# speculator_minor_breakout_54mm_v1.net
KiCad netlist of a schematic drawn in EAGLE
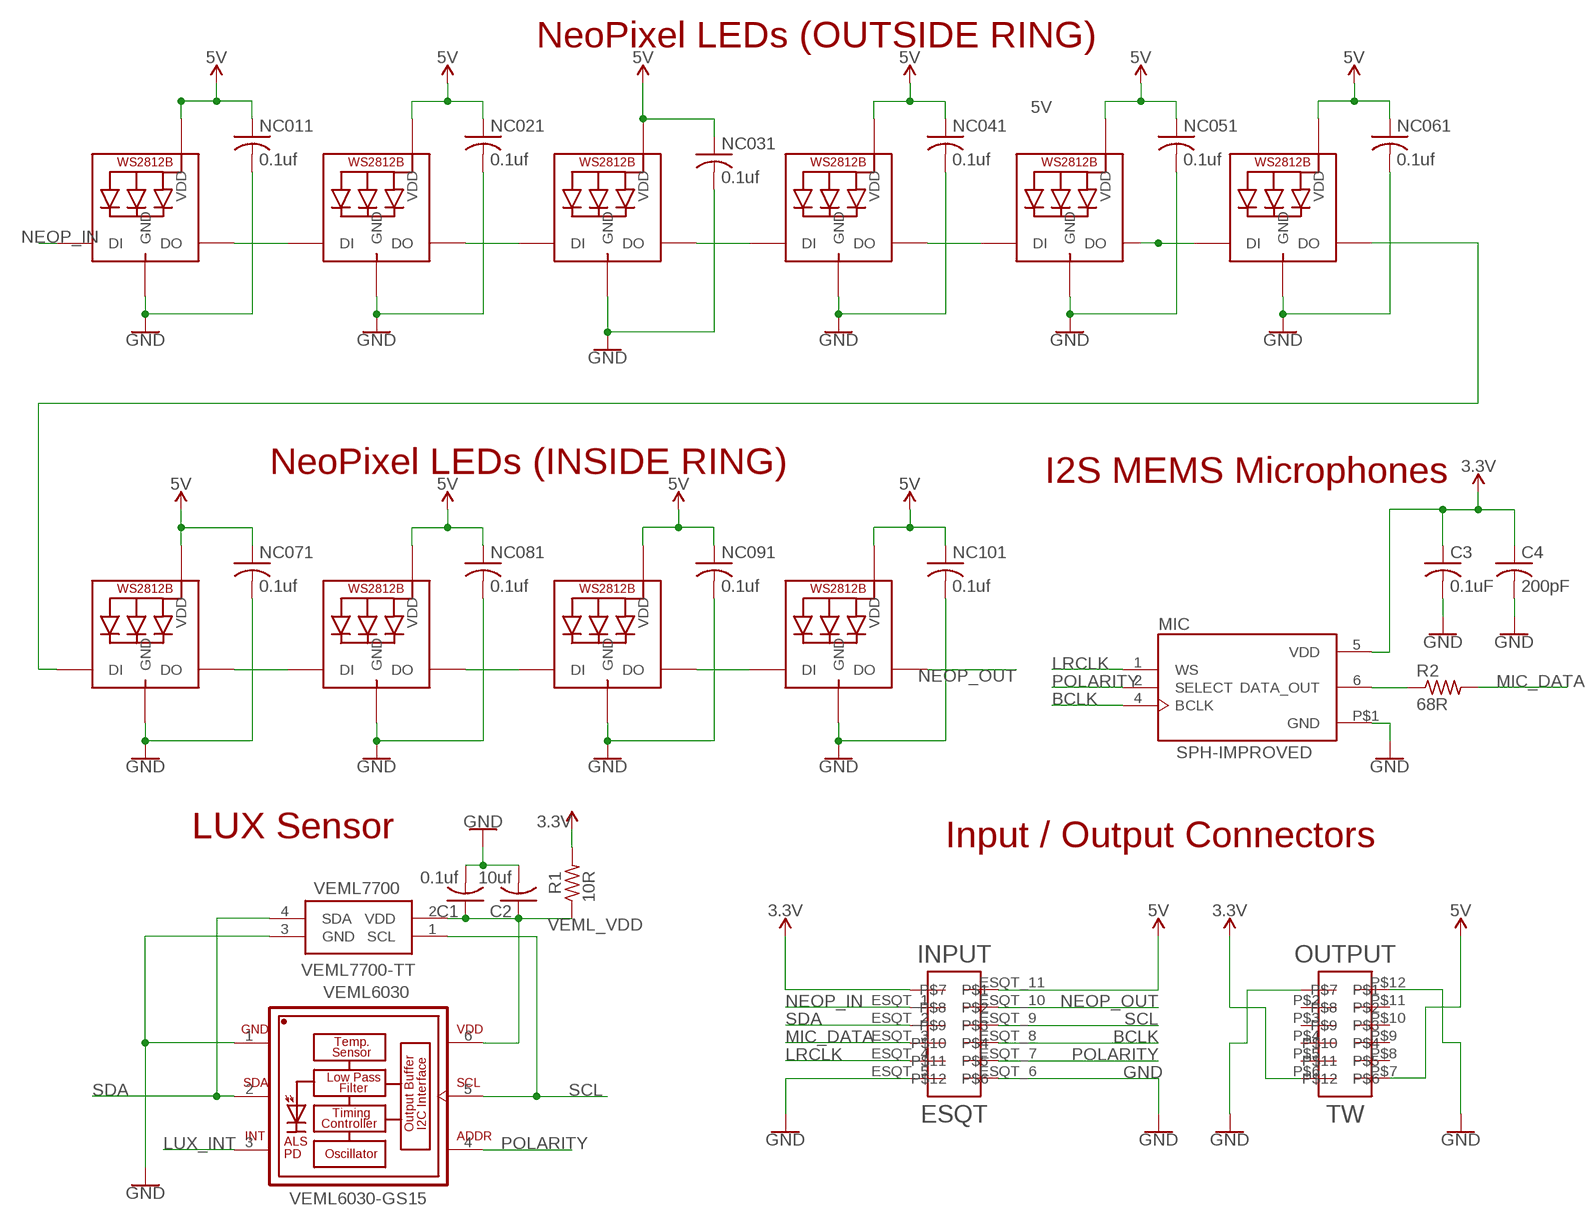
[diagram p0: schematic, sheet 1]

(export (version "E")
  (design (tool "Eeschema 10.0.6"))
  (components
    (comp (ref "C1")
      (value "0.1uf")
      (footprint "eagle-import:C0805")
      (libsource (lib "eagle-import") (part "C-USC0805"))
    )
    (comp (ref "C2")
      (value "10uf")
      (footprint "eagle-import:C0805")
      (libsource (lib "eagle-import") (part "C-USC0805"))
    )
    (comp (ref "C3")
      (value "0.1uF")
      (footprint "eagle-import:C0805")
      (libsource (lib "eagle-import") (part "C-USC0805"))
    )
    (comp (ref "C4")
      (value "200pF")
      (footprint "eagle-import:C0805")
      (libsource (lib "eagle-import") (part "C-USC0805"))
    )
    (comp (ref "INPUT")
      (value "ESQT")
      (footprint "eagle-import:SAMTEC_ESQT_2X6_THROUGH_HOLE")
      (libsource (lib "eagle-import") (part "SAMTEC_ESQT_2X6_THROUGH_HOLE"))
    )
    (comp (ref "MIC")
      (value "SPH-IMPROVED")
      (footprint "eagle-import:MIC_SPH0645LM4H-B_LARGER_RING")
      (libsource (lib "eagle-import") (part "SPH-IMPROVED"))
    )
    (comp (ref "NC011")
      (value "0.1uf")
      (footprint "eagle-import:C0805K")
      (libsource (lib "eagle-import") (part "C-USC0805K"))
    )
    (comp (ref "NC021")
      (value "0.1uf")
      (footprint "eagle-import:C0805K")
      (libsource (lib "eagle-import") (part "C-USC0805K"))
    )
    (comp (ref "NC031")
      (value "0.1uf")
      (footprint "eagle-import:C0805K")
      (libsource (lib "eagle-import") (part "C-USC0805K"))
    )
    (comp (ref "NC041")
      (value "0.1uf")
      (footprint "eagle-import:C0805K")
      (libsource (lib "eagle-import") (part "C-USC0805K"))
    )
    (comp (ref "NC051")
      (value "0.1uf")
      (footprint "eagle-import:C0805K")
      (libsource (lib "eagle-import") (part "C-USC0805K"))
    )
    (comp (ref "NC061")
      (value "0.1uf")
      (footprint "eagle-import:C0805K")
      (libsource (lib "eagle-import") (part "C-USC0805K"))
    )
    (comp (ref "NC071")
      (value "0.1uf")
      (footprint "eagle-import:C0805K")
      (libsource (lib "eagle-import") (part "C-USC0805K"))
    )
    (comp (ref "NC081")
      (value "0.1uf")
      (footprint "eagle-import:C0805K")
      (libsource (lib "eagle-import") (part "C-USC0805K"))
    )
    (comp (ref "NC091")
      (value "0.1uf")
      (footprint "eagle-import:C0805K")
      (libsource (lib "eagle-import") (part "C-USC0805K"))
    )
    (comp (ref "NC101")
      (value "0.1uf")
      (footprint "eagle-import:C0805K")
      (libsource (lib "eagle-import") (part "C-USC0805K"))
    )
    (comp (ref "NEO1")
      (value "WS2812B5050")
      (footprint "eagle-import:WS2812B")
      (libsource (lib "eagle-import") (part "WS2812B5050"))
    )
    (comp (ref "NEO2")
      (value "WS2812B5050")
      (footprint "eagle-import:WS2812B")
      (libsource (lib "eagle-import") (part "WS2812B5050"))
    )
    (comp (ref "NEO3")
      (value "WS2812B5050")
      (footprint "eagle-import:WS2812B")
      (libsource (lib "eagle-import") (part "WS2812B5050"))
    )
    (comp (ref "NEO4")
      (value "WS2812B5050")
      (footprint "eagle-import:WS2812B")
      (libsource (lib "eagle-import") (part "WS2812B5050"))
    )
    (comp (ref "NEO5")
      (value "WS2812B5050")
      (footprint "eagle-import:WS2812B")
      (libsource (lib "eagle-import") (part "WS2812B5050"))
    )
    (comp (ref "NEO6")
      (value "WS2812B5050")
      (footprint "eagle-import:WS2812B")
      (libsource (lib "eagle-import") (part "WS2812B5050"))
    )
    (comp (ref "NEO07")
      (value "WS2812B5050")
      (footprint "eagle-import:WS2812B")
      (libsource (lib "eagle-import") (part "WS2812B5050"))
    )
    (comp (ref "NEO08")
      (value "WS2812B5050")
      (footprint "eagle-import:WS2812B")
      (libsource (lib "eagle-import") (part "WS2812B5050"))
    )
    (comp (ref "NEO9")
      (value "WS2812B5050")
      (footprint "eagle-import:WS2812B")
      (libsource (lib "eagle-import") (part "WS2812B5050"))
    )
    (comp (ref "NEO10")
      (value "WS2812B5050")
      (footprint "eagle-import:WS2812B")
      (libsource (lib "eagle-import") (part "WS2812B5050"))
    )
    (comp (ref "OUTPUT")
      (value "TW")
      (footprint "eagle-import:SAMTEC_TW_2X6")
      (libsource (lib "eagle-import") (part "SAMTEC_TW_2X6_WITH_STABLE"))
    )
    (comp (ref "R1")
      (value "10R")
      (footprint "eagle-import:R0805")
      (libsource (lib "eagle-import") (part "audio amplifier example_970892_R-US_R0805"))
    )
    (comp (ref "R2")
      (value "68R")
      (footprint "eagle-import:M0805")
      (libsource (lib "eagle-import") (part "R-US_M0805"))
    )
    (comp (ref "VEML6030")
      (value "VEML6030-GS15")
      (footprint "eagle-import:VISHAY_VEML6030_2X2X0.87")
      (fields (field (name "MF") "Vishay Semiconductor"))
      (libsource (lib "eagle-import") (part "VEML6030-GS15"))
    )
    (comp (ref "VEML7700")
      (value "VEML7700-TT")
      (footprint "eagle-import:VEML7700")
      (fields (field (name "MOUSER_PART_NUMBER") "78-VEML7700-TT") (field (name "RS_PART_NUMBER") "1226791P"))
      (libsource (lib "eagle-import") (part "VEML7700-TT"))
    )
  )
  (nets
    (net (code "1") (name "/BCLK") (class "Default")
      (node (ref "INPUT") (pin "ESQT_8") (pinfunction "P$10_ESQT_8") (pintype "bidirectional"))
      (node (ref "MIC") (pin "4") (pinfunction "BCLK_4") (pintype "input"))
    )
    (net (code "2") (name "/LRCLK") (class "Default")
      (node (ref "INPUT") (pin "ESQT_4") (pinfunction "P$5_ESQT_4") (pintype "bidirectional"))
      (node (ref "MIC") (pin "1") (pinfunction "WS_1") (pintype "input"))
    )
    (net (code "3") (name "/LUX_INT") (class "Default")
      (node (ref "VEML6030") (pin "3") (pinfunction "INT_3") (pintype "output"))
    )
    (net (code "4") (name "/MIC_DATA") (class "Default")
      (node (ref "INPUT") (pin "ESQT_3") (pinfunction "P$4_ESQT_3") (pintype "bidirectional"))
      (node (ref "R2") (pin "2") (pinfunction "2_2") (pintype "passive"))
    )
    (net (code "5") (name "/NEOP_IN") (class "Default")
      (node (ref "INPUT") (pin "ESQT_1") (pinfunction "P$2_ESQT_1") (pintype "bidirectional"))
      (node (ref "NEO1") (pin "4-DIN") (pinfunction "DI_4-DIN") (pintype "input"))
    )
    (net (code "6") (name "/NEOP_OUT") (class "Default")
      (node (ref "INPUT") (pin "ESQT_10") (pinfunction "P$8_ESQT_10") (pintype "bidirectional"))
      (node (ref "NEO10") (pin "2-DOUT") (pinfunction "DO_2-DOUT") (pintype "output"))
    )
    (net (code "7") (name "/POLARITY") (class "Default")
      (node (ref "INPUT") (pin "ESQT_7") (pinfunction "P$11_ESQT_7") (pintype "bidirectional"))
      (node (ref "MIC") (pin "2") (pinfunction "SELECT_2") (pintype "input"))
      (node (ref "VEML6030") (pin "4") (pinfunction "ADDR_4") (pintype "bidirectional"))
    )
    (net (code "8") (name "/SCL") (class "Default")
      (node (ref "INPUT") (pin "ESQT_9") (pinfunction "P$9_ESQT_9") (pintype "bidirectional"))
      (node (ref "VEML6030") (pin "5") (pinfunction "SCL_5") (pintype "input"))
      (node (ref "VEML7700") (pin "1") (pinfunction "SCL_1") (pintype "bidirectional"))
    )
    (net (code "9") (name "/SDA") (class "Default")
      (node (ref "INPUT") (pin "ESQT_2") (pinfunction "P$3_ESQT_2") (pintype "bidirectional"))
      (node (ref "VEML6030") (pin "2") (pinfunction "SDA_2") (pintype "bidirectional"))
      (node (ref "VEML7700") (pin "4") (pinfunction "SDA_4") (pintype "bidirectional"))
    )
    (net (code "10") (name "/VEML_VDD") (class "Default")
      (node (ref "C1") (pin "1") (pinfunction "1_1") (pintype "passive"))
      (node (ref "C2") (pin "1") (pinfunction "1_1") (pintype "passive"))
      (node (ref "R1") (pin "1") (pinfunction "1_1") (pintype "passive"))
      (node (ref "VEML6030") (pin "6") (pinfunction "VDD_6") (pintype "power_in"))
      (node (ref "VEML7700") (pin "2") (pinfunction "VDD_2") (pintype "bidirectional"))
    )
    (net (code "11") (name "3.3V") (class "Default")
      (node (ref "C3") (pin "1") (pinfunction "1_1") (pintype "passive"))
      (node (ref "C4") (pin "1") (pinfunction "1_1") (pintype "passive"))
      (node (ref "INPUT") (pin "ESQT_0") (pinfunction "P$1_ESQT_0") (pintype "bidirectional"))
      (node (ref "MIC") (pin "5") (pinfunction "VDD_5") (pintype "power_in"))
      (node (ref "OUTPUT") (pin "P$6") (pinfunction "P$6_P$6") (pintype "bidirectional"))
      (node (ref "R1") (pin "2") (pinfunction "2_2") (pintype "passive"))
    )
    (net (code "12") (name "5V") (class "Default")
      (node (ref "INPUT") (pin "ESQT_11") (pinfunction "P$7_ESQT_11") (pintype "bidirectional"))
      (node (ref "NC011") (pin "1") (pinfunction "1_1") (pintype "passive"))
      (node (ref "NC021") (pin "1") (pinfunction "1_1") (pintype "passive"))
      (node (ref "NC031") (pin "1") (pinfunction "1_1") (pintype "passive"))
      (node (ref "NC041") (pin "1") (pinfunction "1_1") (pintype "passive"))
      (node (ref "NC051") (pin "1") (pinfunction "1_1") (pintype "passive"))
      (node (ref "NC061") (pin "1") (pinfunction "1_1") (pintype "passive"))
      (node (ref "NC071") (pin "1") (pinfunction "1_1") (pintype "passive"))
      (node (ref "NC081") (pin "1") (pinfunction "1_1") (pintype "passive"))
      (node (ref "NC091") (pin "1") (pinfunction "1_1") (pintype "passive"))
      (node (ref "NC101") (pin "1") (pinfunction "1_1") (pintype "passive"))
      (node (ref "NEO07") (pin "1-VDD") (pinfunction "VDD_1-VDD") (pintype "power_in"))
      (node (ref "NEO08") (pin "1-VDD") (pinfunction "VDD_1-VDD") (pintype "power_in"))
      (node (ref "NEO1") (pin "1-VDD") (pinfunction "VDD_1-VDD") (pintype "power_in"))
      (node (ref "NEO10") (pin "1-VDD") (pinfunction "VDD_1-VDD") (pintype "power_in"))
      (node (ref "NEO2") (pin "1-VDD") (pinfunction "VDD_1-VDD") (pintype "power_in"))
      (node (ref "NEO3") (pin "1-VDD") (pinfunction "VDD_1-VDD") (pintype "power_in"))
      (node (ref "NEO4") (pin "1-VDD") (pinfunction "VDD_1-VDD") (pintype "power_in"))
      (node (ref "NEO5") (pin "1-VDD") (pinfunction "VDD_1-VDD") (pintype "power_in"))
      (node (ref "NEO6") (pin "1-VDD") (pinfunction "VDD_1-VDD") (pintype "power_in"))
      (node (ref "NEO9") (pin "1-VDD") (pinfunction "VDD_1-VDD") (pintype "power_in"))
      (node (ref "OUTPUT") (pin "P$7") (pinfunction "P$12_P$7") (pintype "bidirectional"))
    )
    (net (code "13") (name "GND") (class "Default")
      (node (ref "C1") (pin "2") (pinfunction "2_2") (pintype "passive"))
      (node (ref "C2") (pin "2") (pinfunction "2_2") (pintype "passive"))
      (node (ref "C3") (pin "2") (pinfunction "2_2") (pintype "passive"))
      (node (ref "C4") (pin "2") (pinfunction "2_2") (pintype "passive"))
      (node (ref "INPUT") (pin "ESQT_5") (pinfunction "P$6_ESQT_5") (pintype "bidirectional"))
      (node (ref "INPUT") (pin "ESQT_6") (pinfunction "P$12_ESQT_6") (pintype "bidirectional"))
      (node (ref "MIC") (pin "P$1") (pinfunction "GND_P$1") (pintype "power_in"))
      (node (ref "NC011") (pin "2") (pinfunction "2_2") (pintype "passive"))
      (node (ref "NC021") (pin "2") (pinfunction "2_2") (pintype "passive"))
      (node (ref "NC031") (pin "2") (pinfunction "2_2") (pintype "passive"))
      (node (ref "NC041") (pin "2") (pinfunction "2_2") (pintype "passive"))
      (node (ref "NC051") (pin "2") (pinfunction "2_2") (pintype "passive"))
      (node (ref "NC061") (pin "2") (pinfunction "2_2") (pintype "passive"))
      (node (ref "NC071") (pin "2") (pinfunction "2_2") (pintype "passive"))
      (node (ref "NC081") (pin "2") (pinfunction "2_2") (pintype "passive"))
      (node (ref "NC091") (pin "2") (pinfunction "2_2") (pintype "passive"))
      (node (ref "NC101") (pin "2") (pinfunction "2_2") (pintype "passive"))
      (node (ref "NEO07") (pin "3-GND") (pinfunction "GND_3-GND") (pintype "power_in"))
      (node (ref "NEO08") (pin "3-GND") (pinfunction "GND_3-GND") (pintype "power_in"))
      (node (ref "NEO1") (pin "3-GND") (pinfunction "GND_3-GND") (pintype "power_in"))
      (node (ref "NEO10") (pin "3-GND") (pinfunction "GND_3-GND") (pintype "power_in"))
      (node (ref "NEO2") (pin "3-GND") (pinfunction "GND_3-GND") (pintype "power_in"))
      (node (ref "NEO3") (pin "3-GND") (pinfunction "GND_3-GND") (pintype "power_in"))
      (node (ref "NEO4") (pin "3-GND") (pinfunction "GND_3-GND") (pintype "power_in"))
      (node (ref "NEO5") (pin "3-GND") (pinfunction "GND_3-GND") (pintype "power_in"))
      (node (ref "NEO6") (pin "3-GND") (pinfunction "GND_3-GND") (pintype "power_in"))
      (node (ref "NEO9") (pin "3-GND") (pinfunction "GND_3-GND") (pintype "power_in"))
      (node (ref "OUTPUT") (pin "P$1") (pinfunction "P$1_P$1") (pintype "bidirectional"))
      (node (ref "OUTPUT") (pin "P$12") (pinfunction "P$7_P$12") (pintype "bidirectional"))
      (node (ref "VEML6030") (pin "1") (pinfunction "GND_1") (pintype "power_in"))
      (node (ref "VEML7700") (pin "3") (pinfunction "GND_3") (pintype "bidirectional"))
    )
    (net (code "14") (name "Net-(MIC-DATA_OUT)") (class "Default")
      (node (ref "MIC") (pin "6") (pinfunction "DATA_OUT_6") (pintype "output"))
      (node (ref "R2") (pin "1") (pinfunction "1_1") (pintype "passive"))
    )
    (net (code "15") (name "Net-(NEO1-DO)") (class "Default")
      (node (ref "NEO1") (pin "2-DOUT") (pinfunction "DO_2-DOUT") (pintype "output"))
      (node (ref "NEO2") (pin "4-DIN") (pinfunction "DI_4-DIN") (pintype "input"))
    )
    (net (code "16") (name "Net-(NEO2-DO)") (class "Default")
      (node (ref "NEO2") (pin "2-DOUT") (pinfunction "DO_2-DOUT") (pintype "output"))
      (node (ref "NEO3") (pin "4-DIN") (pinfunction "DI_4-DIN") (pintype "input"))
    )
    (net (code "17") (name "Net-(NEO3-DO)") (class "Default")
      (node (ref "NEO3") (pin "2-DOUT") (pinfunction "DO_2-DOUT") (pintype "output"))
      (node (ref "NEO4") (pin "4-DIN") (pinfunction "DI_4-DIN") (pintype "input"))
    )
    (net (code "18") (name "Net-(NEO4-DO)") (class "Default")
      (node (ref "NEO4") (pin "2-DOUT") (pinfunction "DO_2-DOUT") (pintype "output"))
      (node (ref "NEO5") (pin "4-DIN") (pinfunction "DI_4-DIN") (pintype "input"))
    )
    (net (code "19") (name "Net-(NEO5-DO)") (class "Default")
      (node (ref "NEO5") (pin "2-DOUT") (pinfunction "DO_2-DOUT") (pintype "output"))
      (node (ref "NEO6") (pin "4-DIN") (pinfunction "DI_4-DIN") (pintype "input"))
    )
    (net (code "20") (name "Net-(NEO07-DI)") (class "Default")
      (node (ref "NEO07") (pin "4-DIN") (pinfunction "DI_4-DIN") (pintype "input"))
      (node (ref "NEO6") (pin "2-DOUT") (pinfunction "DO_2-DOUT") (pintype "output"))
    )
    (net (code "21") (name "Net-(NEO07-DO)") (class "Default")
      (node (ref "NEO07") (pin "2-DOUT") (pinfunction "DO_2-DOUT") (pintype "output"))
      (node (ref "NEO08") (pin "4-DIN") (pinfunction "DI_4-DIN") (pintype "input"))
    )
    (net (code "22") (name "Net-(NEO08-DO)") (class "Default")
      (node (ref "NEO08") (pin "2-DOUT") (pinfunction "DO_2-DOUT") (pintype "output"))
      (node (ref "NEO9") (pin "4-DIN") (pinfunction "DI_4-DIN") (pintype "input"))
    )
    (net (code "23") (name "Net-(NEO10-DI)") (class "Default")
      (node (ref "NEO10") (pin "4-DIN") (pinfunction "DI_4-DIN") (pintype "input"))
      (node (ref "NEO9") (pin "2-DOUT") (pinfunction "DO_2-DOUT") (pintype "output"))
    )
    (net (code "24") (name "unconnected-(OUTPUT-P$8-PadP$11)") (class "Default")
      (node (ref "OUTPUT") (pin "P$11") (pinfunction "P$8_P$11") (pintype "bidirectional"))
    )
    (net (code "25") (name "unconnected-(OUTPUT-P$9-PadP$10)") (class "Default")
      (node (ref "OUTPUT") (pin "P$10") (pinfunction "P$9_P$10") (pintype "bidirectional"))
    )
    (net (code "26") (name "unconnected-(OUTPUT-P$10-PadP$9)") (class "Default")
      (node (ref "OUTPUT") (pin "P$9") (pinfunction "P$10_P$9") (pintype "bidirectional"))
    )
    (net (code "27") (name "unconnected-(OUTPUT-P$11-PadP$8)") (class "Default")
      (node (ref "OUTPUT") (pin "P$8") (pinfunction "P$11_P$8") (pintype "bidirectional"))
    )
    (net (code "28") (name "unconnected-(OUTPUT-PadP$2)") (class "Default")
      (node (ref "OUTPUT") (pin "P$2") (pinfunction "P$2_P$2") (pintype "bidirectional"))
    )
    (net (code "29") (name "unconnected-(OUTPUT-PadP$3)") (class "Default")
      (node (ref "OUTPUT") (pin "P$3") (pinfunction "P$3_P$3") (pintype "bidirectional"))
    )
    (net (code "30") (name "unconnected-(OUTPUT-PadP$4)") (class "Default")
      (node (ref "OUTPUT") (pin "P$4") (pinfunction "P$4_P$4") (pintype "bidirectional"))
    )
    (net (code "31") (name "unconnected-(OUTPUT-PadP$5)") (class "Default")
      (node (ref "OUTPUT") (pin "P$5") (pinfunction "P$5_P$5") (pintype "bidirectional"))
    )
  )
)
